# S7V30_K66BLEZ.net
KiCad netlist of a schematic drawn in Altium Designer
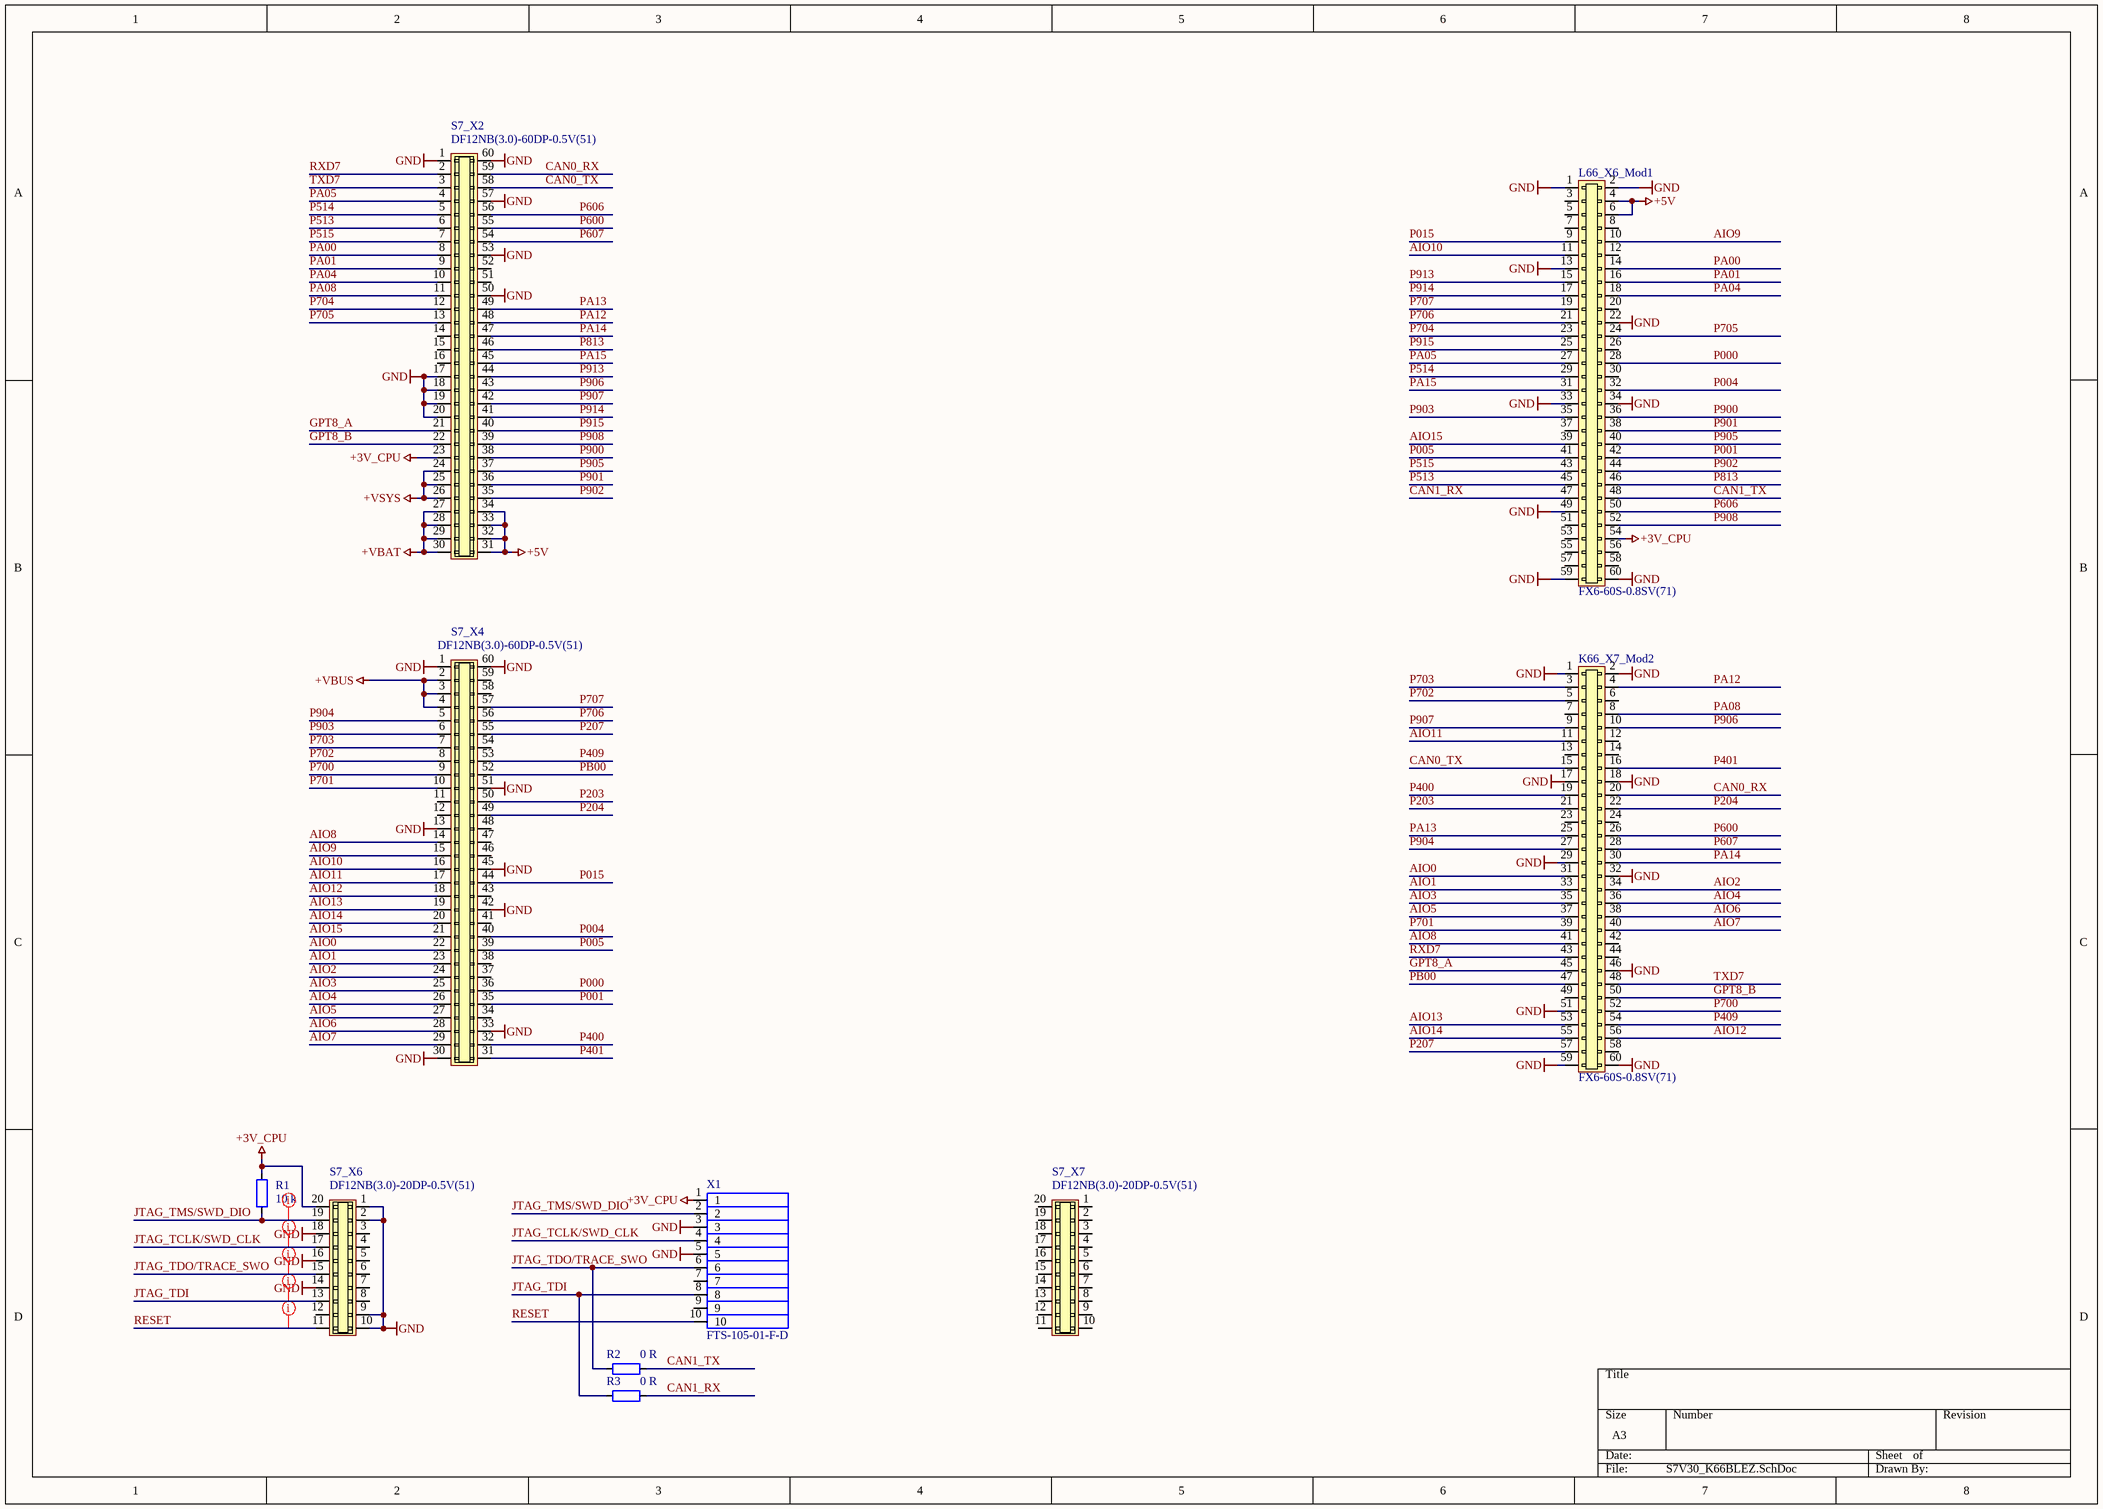
[diagram p0: S7V30_K66BLEZ.SchDoc]

(export (version "E")
  (design (tool "Eeschema 10.0.6"))
  (components
    (comp (ref "K66_X7_Mod2")
      (value "FX6-60S-0.8SV(71)")
      (footprint "FX6-60S-0.8SV(71)")
      (description "RECEPT 60POS .8MM W/BOSS")
      (fields (field (name "MANUFACTURER") "Hirose Electric Co Ltd") (field (name "PARTNUM") "H10806-ND"))
      (libsource (lib "ea_Connectors") (part "FX6-60S-0.8SV(71)"))
    )
    (comp (ref "L66_X6_Mod1")
      (value "FX6-60S-0.8SV(71)")
      (footprint "FX6-60S-0.8SV(71)")
      (description "RECEPT 60POS .8MM W/BOSS")
      (fields (field (name "MANUFACTURER") "Hirose Electric Co Ltd") (field (name "PARTNUM") "H10806-ND"))
      (libsource (lib "ea_Connectors") (part "FX6-60S-0.8SV(71)"))
    )
    (comp (ref "R1")
      (value "10 k")
      (footprint "0402")
      (fields
        (field (name "MANUFACTURER") "Stackpole Electronics Inc")
        (field (name "TOLERANCE") "±1%")
        (field (name "PARTNUM") "RMCF0402FT10K0CT-ND")
      )
      (libsource (lib "ea_PassivComps") (part "Resistor"))
    )
    (comp (ref "R2")
      (value "0 R")
      (footprint "0603")
      (fields
        (field (name "MANUFACTURER") "KOA Speer Electronics, Inc.")
        (field (name "PARTNUM") "2019-RK73Z1JTTDCT-ND")
        (field (name "Comment") "RK73Z1JTTD")
      )
      (libsource (lib "ea_Resistors_0603") (part "RK73Z1JTTD"))
    )
    (comp (ref "R3")
      (value "0 R")
      (footprint "0603")
      (fields
        (field (name "MANUFACTURER") "KOA Speer Electronics, Inc.")
        (field (name "PARTNUM") "2019-RK73Z1JTTDCT-ND")
        (field (name "Comment") "RK73Z1JTTD")
      )
      (libsource (lib "ea_Resistors_0603") (part "RK73Z1JTTD"))
    )
    (comp (ref "S7_X2")
      (value "DF12NB(3.0)-60DP-0.5V(51)")
      (footprint "DF12NB(3.0)-60DP-0.5V(51)")
      (fields
        (field (name "MANUFACTURER") "Hirose Electric")
        (field (name "PARTNUM") "26-DF12NB(3.0)-60DP-0.5V(51)CT-ND - Cut Tape (CT)")
      )
      (libsource (lib "ea_Connectors_0.5_mm_pitch") (part "DF12NB(3.0)-60DP-0.5V(51)"))
    )
    (comp (ref "S7_X4")
      (value "DF12NB(3.0)-60DP-0.5V(51)")
      (footprint "DF12NB(3.0)-60DP-0.5V(51)")
      (fields
        (field (name "MANUFACTURER") "Hirose Electric")
        (field (name "PARTNUM") "26-DF12NB(3.0)-60DP-0.5V(51)CT-ND - Cut Tape (CT)")
      )
      (libsource (lib "ea_Connectors_0.5_mm_pitch") (part "DF12NB(3.0)-60DP-0.5V(51)"))
    )
    (comp (ref "S7_X6")
      (value "DF12NB(3.0)-20DP-0.5V(51)")
      (footprint "DF12NB(3.0)-20DP-0.5V(51)")
      (fields
        (field (name "MANUFACTURER") "Hirose Electric")
        (field (name "PARTNUM") "26-DF12NB(3.0)-20DP-0.5V(51)CT-ND")
      )
      (libsource (lib "ea_Connectors_0.5_mm_pitch") (part "DF12NB(3.0)-20DP-0.5V(51)"))
    )
    (comp (ref "S7_X7")
      (value "DF12NB(3.0)-20DP-0.5V(51)")
      (footprint "DF12NB(3.0)-20DP-0.5V(51)")
      (fields
        (field (name "MANUFACTURER") "Hirose Electric")
        (field (name "PARTNUM") "26-DF12NB(3.0)-20DP-0.5V(51)CT-ND")
      )
      (libsource (lib "ea_Connectors_0.5_mm_pitch") (part "DF12NB(3.0)-20DP-0.5V(51)"))
    )
    (comp (ref "X1")
      (value "FTS-105-01-F-D")
      (footprint "FTS-105-01-F-D")
      (description "Board-To-Board Connector, Vertical, FTS Series, Through Hole, Header, 10, 1.27 mm")
      (fields (field (name "MANUFACTURER") "SAMTEC") (field (name "PARTNUM") "1928242"))
      (libsource (lib "ea_JTAG_SWD") (part "FTS-105-01-F-D"))
    )
  )
  (nets
    (net (code "1") (name "+3V_CPU") (class "Default")
      (node (ref "L66_X6_Mod1") (pin "54") (pinfunction "28_54") (pintype "passive"))
      (node (ref "R1") (pin "2") (pinfunction "2_2") (pintype "passive"))
      (node (ref "S7_X2") (pin "23") (pinfunction "23_23") (pintype "passive"))
      (node (ref "S7_X6") (pin "20") (pinfunction "11_20") (pintype "passive"))
      (node (ref "X1") (pin "1") (pinfunction "1_1") (pintype "passive"))
    )
    (net (code "2") (name "+5V") (class "Default")
      (node (ref "L66_X6_Mod1") (pin "4") (pinfunction "3_4") (pintype "passive"))
      (node (ref "L66_X6_Mod1") (pin "6") (pinfunction "4_6") (pintype "passive"))
      (node (ref "S7_X2") (pin "31") (pinfunction "31_31") (pintype "passive"))
      (node (ref "S7_X2") (pin "32") (pinfunction "32_32") (pintype "passive"))
      (node (ref "S7_X2") (pin "33") (pinfunction "33_33") (pintype "passive"))
      (node (ref "S7_X2") (pin "34") (pinfunction "34_34") (pintype "passive"))
    )
    (net (code "3") (name "+VBAT") (class "Default")
      (node (ref "S7_X2") (pin "27") (pinfunction "27_27") (pintype "passive"))
      (node (ref "S7_X2") (pin "28") (pinfunction "28_28") (pintype "passive"))
      (node (ref "S7_X2") (pin "29") (pinfunction "29_29") (pintype "passive"))
      (node (ref "S7_X2") (pin "30") (pinfunction "30_30") (pintype "passive"))
    )
    (net (code "4") (name "+VBUS") (class "Default")
      (node (ref "S7_X4") (pin "2") (pinfunction "2_2") (pintype "passive"))
      (node (ref "S7_X4") (pin "3") (pinfunction "3_3") (pintype "passive"))
      (node (ref "S7_X4") (pin "4") (pinfunction "4_4") (pintype "passive"))
    )
    (net (code "5") (name "+VSYS") (class "Default")
      (node (ref "S7_X2") (pin "24") (pinfunction "24_24") (pintype "passive"))
      (node (ref "S7_X2") (pin "25") (pinfunction "25_25") (pintype "passive"))
      (node (ref "S7_X2") (pin "26") (pinfunction "26_26") (pintype "passive"))
    )
    (net (code "6") (name "/AIO0") (class "Default")
      (node (ref "K66_X7_Mod2") (pin "31") (pinfunction "16_31") (pintype "passive"))
      (node (ref "S7_X4") (pin "22") (pinfunction "22_22") (pintype "passive"))
    )
    (net (code "7") (name "/AIO1") (class "Default")
      (node (ref "K66_X7_Mod2") (pin "33") (pinfunction "17_33") (pintype "passive"))
      (node (ref "S7_X4") (pin "23") (pinfunction "23_23") (pintype "passive"))
    )
    (net (code "8") (name "/AIO2") (class "Default")
      (node (ref "K66_X7_Mod2") (pin "34") (pinfunction "18_34") (pintype "passive"))
      (node (ref "S7_X4") (pin "24") (pinfunction "24_24") (pintype "passive"))
    )
    (net (code "9") (name "/AIO3") (class "Default")
      (node (ref "K66_X7_Mod2") (pin "35") (pinfunction "18_35") (pintype "passive"))
      (node (ref "S7_X4") (pin "25") (pinfunction "25_25") (pintype "passive"))
    )
    (net (code "10") (name "/AIO4") (class "Default")
      (node (ref "K66_X7_Mod2") (pin "36") (pinfunction "19_36") (pintype "passive"))
      (node (ref "S7_X4") (pin "26") (pinfunction "26_26") (pintype "passive"))
    )
    (net (code "11") (name "/AIO5") (class "Default")
      (node (ref "K66_X7_Mod2") (pin "37") (pinfunction "19_37") (pintype "passive"))
      (node (ref "S7_X4") (pin "27") (pinfunction "27_27") (pintype "passive"))
    )
    (net (code "12") (name "/AIO6") (class "Default")
      (node (ref "K66_X7_Mod2") (pin "38") (pinfunction "20_38") (pintype "passive"))
      (node (ref "S7_X4") (pin "28") (pinfunction "28_28") (pintype "passive"))
    )
    (net (code "13") (name "/AIO7") (class "Default")
      (node (ref "K66_X7_Mod2") (pin "40") (pinfunction "21_40") (pintype "passive"))
      (node (ref "S7_X4") (pin "29") (pinfunction "29_29") (pintype "passive"))
    )
    (net (code "14") (name "/AIO8") (class "Default")
      (node (ref "K66_X7_Mod2") (pin "41") (pinfunction "21_41") (pintype "passive"))
      (node (ref "S7_X4") (pin "14") (pinfunction "14_14") (pintype "passive"))
    )
    (net (code "15") (name "/AIO9") (class "Default")
      (node (ref "L66_X6_Mod1") (pin "10") (pinfunction "6_10") (pintype "passive"))
      (node (ref "S7_X4") (pin "15") (pinfunction "15_15") (pintype "passive"))
    )
    (net (code "16") (name "/AIO10") (class "Default")
      (node (ref "L66_X6_Mod1") (pin "11") (pinfunction "6_11") (pintype "passive"))
      (node (ref "S7_X4") (pin "16") (pinfunction "16_16") (pintype "passive"))
    )
    (net (code "17") (name "/AIO11") (class "Default")
      (node (ref "K66_X7_Mod2") (pin "11") (pinfunction "6_11") (pintype "passive"))
      (node (ref "S7_X4") (pin "17") (pinfunction "17_17") (pintype "passive"))
    )
    (net (code "18") (name "/AIO12") (class "Default")
      (node (ref "K66_X7_Mod2") (pin "56") (pinfunction "29_56") (pintype "passive"))
      (node (ref "S7_X4") (pin "18") (pinfunction "18_18") (pintype "passive"))
    )
    (net (code "19") (name "/AIO13") (class "Default")
      (node (ref "K66_X7_Mod2") (pin "53") (pinfunction "27_53") (pintype "passive"))
      (node (ref "S7_X4") (pin "19") (pinfunction "19_19") (pintype "passive"))
    )
    (net (code "20") (name "/AIO14") (class "Default")
      (node (ref "K66_X7_Mod2") (pin "55") (pinfunction "28_55") (pintype "passive"))
      (node (ref "S7_X4") (pin "20") (pinfunction "20_20") (pintype "passive"))
    )
    (net (code "21") (name "/AIO15") (class "Default")
      (node (ref "L66_X6_Mod1") (pin "39") (pinfunction "20_39") (pintype "passive"))
      (node (ref "S7_X4") (pin "21") (pinfunction "21_21") (pintype "passive"))
    )
    (net (code "22") (name "/CAN0_RX") (class "Default")
      (node (ref "K66_X7_Mod2") (pin "20") (pinfunction "11_20") (pintype "passive"))
      (node (ref "S7_X2") (pin "59") (pinfunction "59_59") (pintype "passive"))
    )
    (net (code "23") (name "/CAN0_TX") (class "Default")
      (node (ref "K66_X7_Mod2") (pin "15") (pinfunction "8_15") (pintype "passive"))
      (node (ref "S7_X2") (pin "58") (pinfunction "58_58") (pintype "passive"))
    )
    (net (code "24") (name "/CAN1_RX") (class "Default")
      (node (ref "L66_X6_Mod1") (pin "47") (pinfunction "24_47") (pintype "passive"))
      (node (ref "R3") (pin "2") (pinfunction "2_2") (pintype "passive"))
    )
    (net (code "25") (name "/CAN1_TX") (class "Default")
      (node (ref "L66_X6_Mod1") (pin "48") (pinfunction "25_48") (pintype "passive"))
      (node (ref "R2") (pin "2") (pinfunction "2_2") (pintype "passive"))
    )
    (net (code "26") (name "/GPT8_A") (class "Default")
      (node (ref "K66_X7_Mod2") (pin "45") (pinfunction "23_45") (pintype "passive"))
      (node (ref "S7_X2") (pin "21") (pinfunction "21_21") (pintype "passive"))
    )
    (net (code "27") (name "/GPT8_B") (class "Default")
      (node (ref "K66_X7_Mod2") (pin "50") (pinfunction "26_50") (pintype "passive"))
      (node (ref "S7_X2") (pin "22") (pinfunction "22_22") (pintype "passive"))
    )
    (net (code "28") (name "/JTAG_TCLK{slash}SWD_CLK") (class "Default")
      (node (ref "S7_X6") (pin "17") (pinfunction "9_17") (pintype "passive"))
      (node (ref "X1") (pin "4") (pinfunction "4_4") (pintype "passive"))
    )
    (net (code "29") (name "/JTAG_TDI") (class "Default")
      (node (ref "R3") (pin "1") (pinfunction "1_1") (pintype "passive"))
      (node (ref "S7_X6") (pin "13") (pinfunction "7_13") (pintype "passive"))
      (node (ref "X1") (pin "8") (pinfunction "8_8") (pintype "power_in"))
    )
    (net (code "30") (name "/JTAG_TDO{slash}TRACE_SWO") (class "Default")
      (node (ref "R2") (pin "1") (pinfunction "1_1") (pintype "passive"))
      (node (ref "S7_X6") (pin "15") (pinfunction "8_15") (pintype "passive"))
      (node (ref "X1") (pin "6") (pinfunction "6_6") (pintype "power_in"))
    )
    (net (code "31") (name "/JTAG_TMS{slash}SWD_DIO") (class "Default")
      (node (ref "R1") (pin "1") (pinfunction "1_1") (pintype "passive"))
      (node (ref "S7_X6") (pin "19") (pinfunction "10_19") (pintype "passive"))
      (node (ref "X1") (pin "2") (pinfunction "2_2") (pintype "passive"))
    )
    (net (code "32") (name "/P000") (class "Default")
      (node (ref "L66_X6_Mod1") (pin "28") (pinfunction "15_28") (pintype "passive"))
      (node (ref "S7_X4") (pin "36") (pinfunction "36_36") (pintype "passive"))
    )
    (net (code "33") (name "/P001") (class "Default")
      (node (ref "L66_X6_Mod1") (pin "42") (pinfunction "22_42") (pintype "passive"))
      (node (ref "S7_X4") (pin "35") (pinfunction "35_35") (pintype "passive"))
    )
    (net (code "34") (name "/P004") (class "Default")
      (node (ref "L66_X6_Mod1") (pin "32") (pinfunction "17_32") (pintype "passive"))
      (node (ref "S7_X4") (pin "40") (pinfunction "40_40") (pintype "passive"))
    )
    (net (code "35") (name "/P005") (class "Default")
      (node (ref "L66_X6_Mod1") (pin "41") (pinfunction "21_41") (pintype "passive"))
      (node (ref "S7_X4") (pin "39") (pinfunction "39_39") (pintype "passive"))
    )
    (net (code "36") (name "/P015") (class "Default")
      (node (ref "L66_X6_Mod1") (pin "9") (pinfunction "5_9") (pintype "passive"))
      (node (ref "S7_X4") (pin "44") (pinfunction "44_44") (pintype "passive"))
    )
    (net (code "37") (name "/P203") (class "Default")
      (node (ref "K66_X7_Mod2") (pin "21") (pinfunction "11_21") (pintype "passive"))
      (node (ref "S7_X4") (pin "50") (pinfunction "50_50") (pintype "passive"))
    )
    (net (code "38") (name "/P204") (class "Default")
      (node (ref "K66_X7_Mod2") (pin "22") (pinfunction "12_22") (pintype "passive"))
      (node (ref "S7_X4") (pin "49") (pinfunction "49_49") (pintype "passive"))
    )
    (net (code "39") (name "/P207") (class "Default")
      (node (ref "K66_X7_Mod2") (pin "57") (pinfunction "29_57") (pintype "passive"))
      (node (ref "S7_X4") (pin "55") (pinfunction "55_55") (pintype "passive"))
    )
    (net (code "40") (name "/P400") (class "Default")
      (node (ref "K66_X7_Mod2") (pin "19") (pinfunction "10_19") (pintype "passive"))
      (node (ref "S7_X4") (pin "32") (pinfunction "32_32") (pintype "passive"))
    )
    (net (code "41") (name "/P401") (class "Default")
      (node (ref "K66_X7_Mod2") (pin "16") (pinfunction "9_16") (pintype "passive"))
      (node (ref "S7_X4") (pin "31") (pinfunction "31_31") (pintype "passive"))
    )
    (net (code "42") (name "/P409") (class "Default")
      (node (ref "K66_X7_Mod2") (pin "54") (pinfunction "28_54") (pintype "passive"))
      (node (ref "S7_X4") (pin "53") (pinfunction "53_53") (pintype "passive"))
    )
    (net (code "43") (name "/P513") (class "Default")
      (node (ref "L66_X6_Mod1") (pin "45") (pinfunction "23_45") (pintype "passive"))
      (node (ref "S7_X2") (pin "6") (pinfunction "6_6") (pintype "passive"))
    )
    (net (code "44") (name "/P514") (class "Default")
      (node (ref "L66_X6_Mod1") (pin "29") (pinfunction "15_29") (pintype "passive"))
      (node (ref "S7_X2") (pin "5") (pinfunction "5_5") (pintype "passive"))
    )
    (net (code "45") (name "/P515") (class "Default")
      (node (ref "L66_X6_Mod1") (pin "43") (pinfunction "22_43") (pintype "passive"))
      (node (ref "S7_X2") (pin "7") (pinfunction "7_7") (pintype "passive"))
    )
    (net (code "46") (name "/P600") (class "Default")
      (node (ref "K66_X7_Mod2") (pin "26") (pinfunction "14_26") (pintype "passive"))
      (node (ref "S7_X2") (pin "55") (pinfunction "55_55") (pintype "passive"))
    )
    (net (code "47") (name "/P606") (class "Default")
      (node (ref "L66_X6_Mod1") (pin "50") (pinfunction "26_50") (pintype "passive"))
      (node (ref "S7_X2") (pin "56") (pinfunction "56_56") (pintype "passive"))
    )
    (net (code "48") (name "/P607") (class "Default")
      (node (ref "K66_X7_Mod2") (pin "28") (pinfunction "15_28") (pintype "passive"))
      (node (ref "S7_X2") (pin "54") (pinfunction "54_54") (pintype "passive"))
    )
    (net (code "49") (name "/P700") (class "Default")
      (node (ref "K66_X7_Mod2") (pin "52") (pinfunction "27_52") (pintype "passive"))
      (node (ref "S7_X4") (pin "9") (pinfunction "9_9") (pintype "passive"))
    )
    (net (code "50") (name "/P701") (class "Default")
      (node (ref "K66_X7_Mod2") (pin "39") (pinfunction "20_39") (pintype "passive"))
      (node (ref "S7_X4") (pin "10") (pinfunction "10_10") (pintype "passive"))
    )
    (net (code "51") (name "/P702") (class "Default")
      (node (ref "K66_X7_Mod2") (pin "5") (pinfunction "3_5") (pintype "passive"))
      (node (ref "S7_X4") (pin "8") (pinfunction "8_8") (pintype "passive"))
    )
    (net (code "52") (name "/P703") (class "Default")
      (node (ref "K66_X7_Mod2") (pin "3") (pinfunction "2_3") (pintype "passive"))
      (node (ref "S7_X4") (pin "7") (pinfunction "7_7") (pintype "passive"))
    )
    (net (code "53") (name "/P704") (class "Default")
      (node (ref "L66_X6_Mod1") (pin "23") (pinfunction "12_23") (pintype "passive"))
      (node (ref "S7_X2") (pin "12") (pinfunction "12_12") (pintype "passive"))
    )
    (net (code "54") (name "/P705") (class "Default")
      (node (ref "L66_X6_Mod1") (pin "24") (pinfunction "13_24") (pintype "passive"))
      (node (ref "S7_X2") (pin "13") (pinfunction "13_13") (pintype "passive"))
    )
    (net (code "55") (name "/P706") (class "Default")
      (node (ref "L66_X6_Mod1") (pin "21") (pinfunction "11_21") (pintype "passive"))
      (node (ref "S7_X4") (pin "56") (pinfunction "56_56") (pintype "passive"))
    )
    (net (code "56") (name "/P707") (class "Default")
      (node (ref "L66_X6_Mod1") (pin "19") (pinfunction "10_19") (pintype "passive"))
      (node (ref "S7_X4") (pin "57") (pinfunction "57_57") (pintype "passive"))
    )
    (net (code "57") (name "/P813") (class "Default")
      (node (ref "L66_X6_Mod1") (pin "46") (pinfunction "24_46") (pintype "passive"))
      (node (ref "S7_X2") (pin "46") (pinfunction "46_46") (pintype "passive"))
    )
    (net (code "58") (name "/P900") (class "Default")
      (node (ref "L66_X6_Mod1") (pin "36") (pinfunction "19_36") (pintype "passive"))
      (node (ref "S7_X2") (pin "38") (pinfunction "38_38") (pintype "passive"))
    )
    (net (code "59") (name "/P901") (class "Default")
      (node (ref "L66_X6_Mod1") (pin "38") (pinfunction "20_38") (pintype "passive"))
      (node (ref "S7_X2") (pin "36") (pinfunction "36_36") (pintype "passive"))
    )
    (net (code "60") (name "/P902") (class "Default")
      (node (ref "L66_X6_Mod1") (pin "44") (pinfunction "23_44") (pintype "passive"))
      (node (ref "S7_X2") (pin "35") (pinfunction "35_35") (pintype "passive"))
    )
    (net (code "61") (name "/P903") (class "Default")
      (node (ref "L66_X6_Mod1") (pin "35") (pinfunction "18_35") (pintype "passive"))
      (node (ref "S7_X4") (pin "6") (pinfunction "6_6") (pintype "passive"))
    )
    (net (code "62") (name "/P904") (class "Default")
      (node (ref "K66_X7_Mod2") (pin "27") (pinfunction "14_27") (pintype "passive"))
      (node (ref "S7_X4") (pin "5") (pinfunction "5_5") (pintype "passive"))
    )
    (net (code "63") (name "/P905") (class "Default")
      (node (ref "L66_X6_Mod1") (pin "40") (pinfunction "21_40") (pintype "passive"))
      (node (ref "S7_X2") (pin "37") (pinfunction "37_37") (pintype "passive"))
    )
    (net (code "64") (name "/P906") (class "Default")
      (node (ref "K66_X7_Mod2") (pin "10") (pinfunction "6_10") (pintype "passive"))
      (node (ref "S7_X2") (pin "43") (pinfunction "43_43") (pintype "passive"))
    )
    (net (code "65") (name "/P907") (class "Default")
      (node (ref "K66_X7_Mod2") (pin "9") (pinfunction "5_9") (pintype "passive"))
      (node (ref "S7_X2") (pin "42") (pinfunction "42_42") (pintype "passive"))
    )
    (net (code "66") (name "/P908") (class "Default")
      (node (ref "L66_X6_Mod1") (pin "52") (pinfunction "27_52") (pintype "passive"))
      (node (ref "S7_X2") (pin "39") (pinfunction "39_39") (pintype "passive"))
    )
    (net (code "67") (name "/P913") (class "Default")
      (node (ref "L66_X6_Mod1") (pin "15") (pinfunction "8_15") (pintype "passive"))
      (node (ref "S7_X2") (pin "44") (pinfunction "44_44") (pintype "passive"))
    )
    (net (code "68") (name "/P914") (class "Default")
      (node (ref "L66_X6_Mod1") (pin "17") (pinfunction "9_17") (pintype "passive"))
      (node (ref "S7_X2") (pin "41") (pinfunction "41_41") (pintype "passive"))
    )
    (net (code "69") (name "/P915") (class "Default")
      (node (ref "L66_X6_Mod1") (pin "25") (pinfunction "13_25") (pintype "passive"))
      (node (ref "S7_X2") (pin "40") (pinfunction "40_40") (pintype "passive"))
    )
    (net (code "70") (name "/PA00") (class "Default")
      (node (ref "L66_X6_Mod1") (pin "14") (pinfunction "8_14") (pintype "passive"))
      (node (ref "S7_X2") (pin "8") (pinfunction "8_8") (pintype "passive"))
    )
    (net (code "71") (name "/PA01") (class "Default")
      (node (ref "L66_X6_Mod1") (pin "16") (pinfunction "9_16") (pintype "passive"))
      (node (ref "S7_X2") (pin "9") (pinfunction "9_9") (pintype "passive"))
    )
    (net (code "72") (name "/PA04") (class "Default")
      (node (ref "L66_X6_Mod1") (pin "18") (pinfunction "10_18") (pintype "passive"))
      (node (ref "S7_X2") (pin "10") (pinfunction "10_10") (pintype "passive"))
    )
    (net (code "73") (name "/PA05") (class "Default")
      (node (ref "L66_X6_Mod1") (pin "27") (pinfunction "14_27") (pintype "passive"))
      (node (ref "S7_X2") (pin "4") (pinfunction "4_4") (pintype "passive"))
    )
    (net (code "74") (name "/PA08") (class "Default")
      (node (ref "K66_X7_Mod2") (pin "8") (pinfunction "5_8") (pintype "passive"))
      (node (ref "S7_X2") (pin "11") (pinfunction "11_11") (pintype "passive"))
    )
    (net (code "75") (name "/PA12") (class "Default")
      (node (ref "K66_X7_Mod2") (pin "4") (pinfunction "3_4") (pintype "passive"))
      (node (ref "S7_X2") (pin "48") (pinfunction "48_48") (pintype "passive"))
    )
    (net (code "76") (name "/PA13") (class "Default")
      (node (ref "K66_X7_Mod2") (pin "25") (pinfunction "13_25") (pintype "passive"))
      (node (ref "S7_X2") (pin "49") (pinfunction "49_49") (pintype "passive"))
    )
    (net (code "77") (name "/PA14") (class "Default")
      (node (ref "K66_X7_Mod2") (pin "30") (pinfunction "16_30") (pintype "passive"))
      (node (ref "S7_X2") (pin "47") (pinfunction "47_47") (pintype "passive"))
    )
    (net (code "78") (name "/PA15") (class "Default")
      (node (ref "L66_X6_Mod1") (pin "31") (pinfunction "16_31") (pintype "passive"))
      (node (ref "S7_X2") (pin "45") (pinfunction "45_45") (pintype "passive"))
    )
    (net (code "79") (name "/PB00") (class "Default")
      (node (ref "K66_X7_Mod2") (pin "47") (pinfunction "24_47") (pintype "passive"))
      (node (ref "S7_X4") (pin "52") (pinfunction "52_52") (pintype "passive"))
    )
    (net (code "80") (name "/RESET") (class "Default")
      (node (ref "S7_X6") (pin "11") (pinfunction "6_11") (pintype "passive"))
      (node (ref "X1") (pin "10") (pinfunction "10_10") (pintype "power_in"))
    )
    (net (code "81") (name "/RXD7") (class "Default")
      (node (ref "K66_X7_Mod2") (pin "43") (pinfunction "22_43") (pintype "passive"))
      (node (ref "S7_X2") (pin "2") (pinfunction "2_2") (pintype "passive"))
    )
    (net (code "82") (name "/TXD7") (class "Default")
      (node (ref "K66_X7_Mod2") (pin "48") (pinfunction "25_48") (pintype "passive"))
      (node (ref "S7_X2") (pin "3") (pinfunction "3_3") (pintype "passive"))
    )
    (net (code "83") (name "GND") (class "Default")
      (node (ref "K66_X7_Mod2") (pin "1") (pinfunction "1_1") (pintype "passive"))
      (node (ref "K66_X7_Mod2") (pin "17") (pinfunction "9_17") (pintype "passive"))
      (node (ref "K66_X7_Mod2") (pin "18") (pinfunction "10_18") (pintype "passive"))
      (node (ref "K66_X7_Mod2") (pin "2") (pinfunction "2_2") (pintype "passive"))
      (node (ref "K66_X7_Mod2") (pin "29") (pinfunction "15_29") (pintype "passive"))
      (node (ref "K66_X7_Mod2") (pin "32") (pinfunction "17_32") (pintype "passive"))
      (node (ref "K66_X7_Mod2") (pin "46") (pinfunction "24_46") (pintype "passive"))
      (node (ref "K66_X7_Mod2") (pin "51") (pinfunction "26_51") (pintype "passive"))
      (node (ref "K66_X7_Mod2") (pin "59") (pinfunction "30_59") (pintype "passive"))
      (node (ref "K66_X7_Mod2") (pin "60") (pinfunction "31_60") (pintype "passive"))
      (node (ref "L66_X6_Mod1") (pin "1") (pinfunction "1_1") (pintype "passive"))
      (node (ref "L66_X6_Mod1") (pin "13") (pinfunction "7_13") (pintype "passive"))
      (node (ref "L66_X6_Mod1") (pin "2") (pinfunction "2_2") (pintype "passive"))
      (node (ref "L66_X6_Mod1") (pin "22") (pinfunction "12_22") (pintype "passive"))
      (node (ref "L66_X6_Mod1") (pin "33") (pinfunction "17_33") (pintype "passive"))
      (node (ref "L66_X6_Mod1") (pin "34") (pinfunction "18_34") (pintype "passive"))
      (node (ref "L66_X6_Mod1") (pin "49") (pinfunction "25_49") (pintype "passive"))
      (node (ref "L66_X6_Mod1") (pin "59") (pinfunction "30_59") (pintype "passive"))
      (node (ref "L66_X6_Mod1") (pin "60") (pinfunction "31_60") (pintype "passive"))
      (node (ref "S7_X2") (pin "1") (pinfunction "1_1") (pintype "passive"))
      (node (ref "S7_X2") (pin "17") (pinfunction "17_17") (pintype "passive"))
      (node (ref "S7_X2") (pin "18") (pinfunction "18_18") (pintype "passive"))
      (node (ref "S7_X2") (pin "19") (pinfunction "19_19") (pintype "passive"))
      (node (ref "S7_X2") (pin "20") (pinfunction "20_20") (pintype "passive"))
      (node (ref "S7_X2") (pin "50") (pinfunction "50_50") (pintype "passive"))
      (node (ref "S7_X2") (pin "53") (pinfunction "53_53") (pintype "passive"))
      (node (ref "S7_X2") (pin "57") (pinfunction "57_57") (pintype "passive"))
      (node (ref "S7_X2") (pin "60") (pinfunction "60_60") (pintype "passive"))
      (node (ref "S7_X4") (pin "1") (pinfunction "1_1") (pintype "passive"))
      (node (ref "S7_X4") (pin "13") (pinfunction "13_13") (pintype "passive"))
      (node (ref "S7_X4") (pin "30") (pinfunction "30_30") (pintype "passive"))
      (node (ref "S7_X4") (pin "33") (pinfunction "33_33") (pintype "passive"))
      (node (ref "S7_X4") (pin "42") (pinfunction "42_42") (pintype "passive"))
      (node (ref "S7_X4") (pin "45") (pinfunction "45_45") (pintype "passive"))
      (node (ref "S7_X4") (pin "51") (pinfunction "51_51") (pintype "passive"))
      (node (ref "S7_X4") (pin "60") (pinfunction "60_60") (pintype "passive"))
      (node (ref "S7_X6") (pin "1") (pinfunction "1_1") (pintype "passive"))
      (node (ref "S7_X6") (pin "10") (pinfunction "6_10") (pintype "passive"))
      (node (ref "S7_X6") (pin "14") (pinfunction "8_14") (pintype "passive"))
      (node (ref "S7_X6") (pin "16") (pinfunction "9_16") (pintype "passive"))
      (node (ref "S7_X6") (pin "18") (pinfunction "10_18") (pintype "passive"))
      (node (ref "S7_X6") (pin "2") (pinfunction "2_2") (pintype "passive"))
      (node (ref "S7_X6") (pin "9") (pinfunction "5_9") (pintype "passive"))
      (node (ref "X1") (pin "3") (pinfunction "3_3") (pintype "passive"))
      (node (ref "X1") (pin "5") (pinfunction "5_5") (pintype "power_in"))
    )
    (net (code "84") (name "unconnected-(K66_X7_Mod2-4-Pad6)") (class "Default")
      (node (ref "K66_X7_Mod2") (pin "6") (pinfunction "4_6") (pintype "passive"))
    )
    (net (code "85") (name "unconnected-(K66_X7_Mod2-4-Pad7)") (class "Default")
      (node (ref "K66_X7_Mod2") (pin "7") (pinfunction "4_7") (pintype "passive"))
    )
    (net (code "86") (name "unconnected-(K66_X7_Mod2-7-Pad12)") (class "Default")
      (node (ref "K66_X7_Mod2") (pin "12") (pinfunction "7_12") (pintype "passive"))
    )
    (net (code "87") (name "unconnected-(K66_X7_Mod2-7-Pad13)") (class "Default")
      (node (ref "K66_X7_Mod2") (pin "13") (pinfunction "7_13") (pintype "passive"))
    )
    (net (code "88") (name "unconnected-(K66_X7_Mod2-8-Pad14)") (class "Default")
      (node (ref "K66_X7_Mod2") (pin "14") (pinfunction "8_14") (pintype "passive"))
    )
    (net (code "89") (name "unconnected-(K66_X7_Mod2-12-Pad23)") (class "Default")
      (node (ref "K66_X7_Mod2") (pin "23") (pinfunction "12_23") (pintype "passive"))
    )
    (net (code "90") (name "unconnected-(K66_X7_Mod2-13-Pad24)") (class "Default")
      (node (ref "K66_X7_Mod2") (pin "24") (pinfunction "13_24") (pintype "passive"))
    )
    (net (code "91") (name "unconnected-(K66_X7_Mod2-22-Pad42)") (class "Default")
      (node (ref "K66_X7_Mod2") (pin "42") (pinfunction "22_42") (pintype "passive"))
    )
    (net (code "92") (name "unconnected-(K66_X7_Mod2-23-Pad44)") (class "Default")
      (node (ref "K66_X7_Mod2") (pin "44") (pinfunction "23_44") (pintype "passive"))
    )
    (net (code "93") (name "unconnected-(K66_X7_Mod2-25-Pad49)") (class "Default")
      (node (ref "K66_X7_Mod2") (pin "49") (pinfunction "25_49") (pintype "passive"))
    )
    (net (code "94") (name "unconnected-(K66_X7_Mod2-30-Pad58)") (class "Default")
      (node (ref "K66_X7_Mod2") (pin "58") (pinfunction "30_58") (pintype "passive"))
    )
    (net (code "95") (name "unconnected-(L66_X6_Mod1-2-Pad3)") (class "Default")
      (node (ref "L66_X6_Mod1") (pin "3") (pinfunction "2_3") (pintype "passive"))
    )
    (net (code "96") (name "unconnected-(L66_X6_Mod1-3-Pad5)") (class "Default")
      (node (ref "L66_X6_Mod1") (pin "5") (pinfunction "3_5") (pintype "passive"))
    )
    (net (code "97") (name "unconnected-(L66_X6_Mod1-4-Pad7)") (class "Default")
      (node (ref "L66_X6_Mod1") (pin "7") (pinfunction "4_7") (pintype "passive"))
    )
    (net (code "98") (name "unconnected-(L66_X6_Mod1-5-Pad8)") (class "Default")
      (node (ref "L66_X6_Mod1") (pin "8") (pinfunction "5_8") (pintype "passive"))
    )
    (net (code "99") (name "unconnected-(L66_X6_Mod1-7-Pad12)") (class "Default")
      (node (ref "L66_X6_Mod1") (pin "12") (pinfunction "7_12") (pintype "passive"))
    )
    (net (code "100") (name "unconnected-(L66_X6_Mod1-11-Pad20)") (class "Default")
      (node (ref "L66_X6_Mod1") (pin "20") (pinfunction "11_20") (pintype "passive"))
    )
    (net (code "101") (name "unconnected-(L66_X6_Mod1-14-Pad26)") (class "Default")
      (node (ref "L66_X6_Mod1") (pin "26") (pinfunction "14_26") (pintype "passive"))
    )
    (net (code "102") (name "unconnected-(L66_X6_Mod1-16-Pad30)") (class "Default")
      (node (ref "L66_X6_Mod1") (pin "30") (pinfunction "16_30") (pintype "passive"))
    )
    (net (code "103") (name "unconnected-(L66_X6_Mod1-19-Pad37)") (class "Default")
      (node (ref "L66_X6_Mod1") (pin "37") (pinfunction "19_37") (pintype "passive"))
    )
    (net (code "104") (name "unconnected-(L66_X6_Mod1-26-Pad51)") (class "Default")
      (node (ref "L66_X6_Mod1") (pin "51") (pinfunction "26_51") (pintype "passive"))
    )
    (net (code "105") (name "unconnected-(L66_X6_Mod1-27-Pad53)") (class "Default")
      (node (ref "L66_X6_Mod1") (pin "53") (pinfunction "27_53") (pintype "passive"))
    )
    (net (code "106") (name "unconnected-(L66_X6_Mod1-28-Pad55)") (class "Default")
      (node (ref "L66_X6_Mod1") (pin "55") (pinfunction "28_55") (pintype "passive"))
    )
    (net (code "107") (name "unconnected-(L66_X6_Mod1-29-Pad56)") (class "Default")
      (node (ref "L66_X6_Mod1") (pin "56") (pinfunction "29_56") (pintype "passive"))
    )
    (net (code "108") (name "unconnected-(L66_X6_Mod1-29-Pad57)") (class "Default")
      (node (ref "L66_X6_Mod1") (pin "57") (pinfunction "29_57") (pintype "passive"))
    )
    (net (code "109") (name "unconnected-(L66_X6_Mod1-30-Pad58)") (class "Default")
      (node (ref "L66_X6_Mod1") (pin "58") (pinfunction "30_58") (pintype "passive"))
    )
    (net (code "110") (name "unconnected-(S7_X2-Pad14)") (class "Default")
      (node (ref "S7_X2") (pin "14") (pinfunction "14_14") (pintype "passive"))
    )
    (net (code "111") (name "unconnected-(S7_X2-Pad15)") (class "Default")
      (node (ref "S7_X2") (pin "15") (pinfunction "15_15") (pintype "passive"))
    )
    (net (code "112") (name "unconnected-(S7_X2-Pad16)") (class "Default")
      (node (ref "S7_X2") (pin "16") (pinfunction "16_16") (pintype "passive"))
    )
    (net (code "113") (name "unconnected-(S7_X2-Pad51)") (class "Default")
      (node (ref "S7_X2") (pin "51") (pinfunction "51_51") (pintype "passive"))
    )
    (net (code "114") (name "unconnected-(S7_X2-Pad52)") (class "Default")
      (node (ref "S7_X2") (pin "52") (pinfunction "52_52") (pintype "passive"))
    )
    (net (code "115") (name "unconnected-(S7_X4-Pad11)") (class "Default")
      (node (ref "S7_X4") (pin "11") (pinfunction "11_11") (pintype "passive"))
    )
    (net (code "116") (name "unconnected-(S7_X4-Pad12)") (class "Default")
      (node (ref "S7_X4") (pin "12") (pinfunction "12_12") (pintype "passive"))
    )
    (net (code "117") (name "unconnected-(S7_X4-Pad34)") (class "Default")
      (node (ref "S7_X4") (pin "34") (pinfunction "34_34") (pintype "passive"))
    )
    (net (code "118") (name "unconnected-(S7_X4-Pad37)") (class "Default")
      (node (ref "S7_X4") (pin "37") (pinfunction "37_37") (pintype "passive"))
    )
    (net (code "119") (name "unconnected-(S7_X4-Pad38)") (class "Default")
      (node (ref "S7_X4") (pin "38") (pinfunction "38_38") (pintype "passive"))
    )
    (net (code "120") (name "unconnected-(S7_X4-Pad41)") (class "Default")
      (node (ref "S7_X4") (pin "41") (pinfunction "41_41") (pintype "passive"))
    )
    (net (code "121") (name "unconnected-(S7_X4-Pad43)") (class "Default")
      (node (ref "S7_X4") (pin "43") (pinfunction "43_43") (pintype "passive"))
    )
    (net (code "122") (name "unconnected-(S7_X4-Pad46)") (class "Default")
      (node (ref "S7_X4") (pin "46") (pinfunction "46_46") (pintype "passive"))
    )
    (net (code "123") (name "unconnected-(S7_X4-Pad47)") (class "Default")
      (node (ref "S7_X4") (pin "47") (pinfunction "47_47") (pintype "passive"))
    )
    (net (code "124") (name "unconnected-(S7_X4-Pad48)") (class "Default")
      (node (ref "S7_X4") (pin "48") (pinfunction "48_48") (pintype "passive"))
    )
    (net (code "125") (name "unconnected-(S7_X4-Pad54)") (class "Default")
      (node (ref "S7_X4") (pin "54") (pinfunction "54_54") (pintype "passive"))
    )
    (net (code "126") (name "unconnected-(S7_X4-Pad58)") (class "Default")
      (node (ref "S7_X4") (pin "58") (pinfunction "58_58") (pintype "passive"))
    )
    (net (code "127") (name "unconnected-(S7_X4-Pad59)") (class "Default")
      (node (ref "S7_X4") (pin "59") (pinfunction "59_59") (pintype "passive"))
    )
    (net (code "128") (name "unconnected-(S7_X6-2-Pad3)") (class "Default")
      (node (ref "S7_X6") (pin "3") (pinfunction "2_3") (pintype "passive"))
    )
    (net (code "129") (name "unconnected-(S7_X6-3-Pad4)") (class "Default")
      (node (ref "S7_X6") (pin "4") (pinfunction "3_4") (pintype "passive"))
    )
    (net (code "130") (name "unconnected-(S7_X6-3-Pad5)") (class "Default")
      (node (ref "S7_X6") (pin "5") (pinfunction "3_5") (pintype "passive"))
    )
    (net (code "131") (name "unconnected-(S7_X6-4-Pad6)") (class "Default")
      (node (ref "S7_X6") (pin "6") (pinfunction "4_6") (pintype "passive"))
    )
    (net (code "132") (name "unconnected-(S7_X6-4-Pad7)") (class "Default")
      (node (ref "S7_X6") (pin "7") (pinfunction "4_7") (pintype "passive"))
    )
    (net (code "133") (name "unconnected-(S7_X6-5-Pad8)") (class "Default")
      (node (ref "S7_X6") (pin "8") (pinfunction "5_8") (pintype "passive"))
    )
    (net (code "134") (name "unconnected-(S7_X6-7-Pad12)") (class "Default")
      (node (ref "S7_X6") (pin "12") (pinfunction "7_12") (pintype "passive"))
    )
    (net (code "135") (name "unconnected-(S7_X7-2-Pad3)") (class "Default")
      (node (ref "S7_X7") (pin "3") (pinfunction "2_3") (pintype "passive"))
    )
    (net (code "136") (name "unconnected-(S7_X7-3-Pad4)") (class "Default")
      (node (ref "S7_X7") (pin "4") (pinfunction "3_4") (pintype "passive"))
    )
    (net (code "137") (name "unconnected-(S7_X7-3-Pad5)") (class "Default")
      (node (ref "S7_X7") (pin "5") (pinfunction "3_5") (pintype "passive"))
    )
    (net (code "138") (name "unconnected-(S7_X7-4-Pad6)") (class "Default")
      (node (ref "S7_X7") (pin "6") (pinfunction "4_6") (pintype "passive"))
    )
    (net (code "139") (name "unconnected-(S7_X7-4-Pad7)") (class "Default")
      (node (ref "S7_X7") (pin "7") (pinfunction "4_7") (pintype "passive"))
    )
    (net (code "140") (name "unconnected-(S7_X7-5-Pad8)") (class "Default")
      (node (ref "S7_X7") (pin "8") (pinfunction "5_8") (pintype "passive"))
    )
    (net (code "141") (name "unconnected-(S7_X7-5-Pad9)") (class "Default")
      (node (ref "S7_X7") (pin "9") (pinfunction "5_9") (pintype "passive"))
    )
    (net (code "142") (name "unconnected-(S7_X7-6-Pad10)") (class "Default")
      (node (ref "S7_X7") (pin "10") (pinfunction "6_10") (pintype "passive"))
    )
    (net (code "143") (name "unconnected-(S7_X7-6-Pad11)") (class "Default")
      (node (ref "S7_X7") (pin "11") (pinfunction "6_11") (pintype "passive"))
    )
    (net (code "144") (name "unconnected-(S7_X7-7-Pad12)") (class "Default")
      (node (ref "S7_X7") (pin "12") (pinfunction "7_12") (pintype "passive"))
    )
    (net (code "145") (name "unconnected-(S7_X7-7-Pad13)") (class "Default")
      (node (ref "S7_X7") (pin "13") (pinfunction "7_13") (pintype "passive"))
    )
    (net (code "146") (name "unconnected-(S7_X7-8-Pad14)") (class "Default")
      (node (ref "S7_X7") (pin "14") (pinfunction "8_14") (pintype "passive"))
    )
    (net (code "147") (name "unconnected-(S7_X7-8-Pad15)") (class "Default")
      (node (ref "S7_X7") (pin "15") (pinfunction "8_15") (pintype "passive"))
    )
    (net (code "148") (name "unconnected-(S7_X7-9-Pad16)") (class "Default")
      (node (ref "S7_X7") (pin "16") (pinfunction "9_16") (pintype "passive"))
    )
    (net (code "149") (name "unconnected-(S7_X7-9-Pad17)") (class "Default")
      (node (ref "S7_X7") (pin "17") (pinfunction "9_17") (pintype "passive"))
    )
    (net (code "150") (name "unconnected-(S7_X7-10-Pad18)") (class "Default")
      (node (ref "S7_X7") (pin "18") (pinfunction "10_18") (pintype "passive"))
    )
    (net (code "151") (name "unconnected-(S7_X7-10-Pad19)") (class "Default")
      (node (ref "S7_X7") (pin "19") (pinfunction "10_19") (pintype "passive"))
    )
    (net (code "152") (name "unconnected-(S7_X7-11-Pad20)") (class "Default")
      (node (ref "S7_X7") (pin "20") (pinfunction "11_20") (pintype "passive"))
    )
    (net (code "153") (name "unconnected-(S7_X7-Pad1)") (class "Default")
      (node (ref "S7_X7") (pin "1") (pinfunction "1_1") (pintype "passive"))
    )
    (net (code "154") (name "unconnected-(S7_X7-Pad2)") (class "Default")
      (node (ref "S7_X7") (pin "2") (pinfunction "2_2") (pintype "passive"))
    )
    (net (code "155") (name "unconnected-(X1-Pad7)") (class "Default")
      (node (ref "X1") (pin "7") (pinfunction "7_7") (pintype "power_in"))
    )
    (net (code "156") (name "unconnected-(X1-Pad9)") (class "Default")
      (node (ref "X1") (pin "9") (pinfunction "9_9") (pintype "power_in"))
    )
  )
)
